# rxfirst.net
KiCad netlist of a schematic drawn in EAGLE
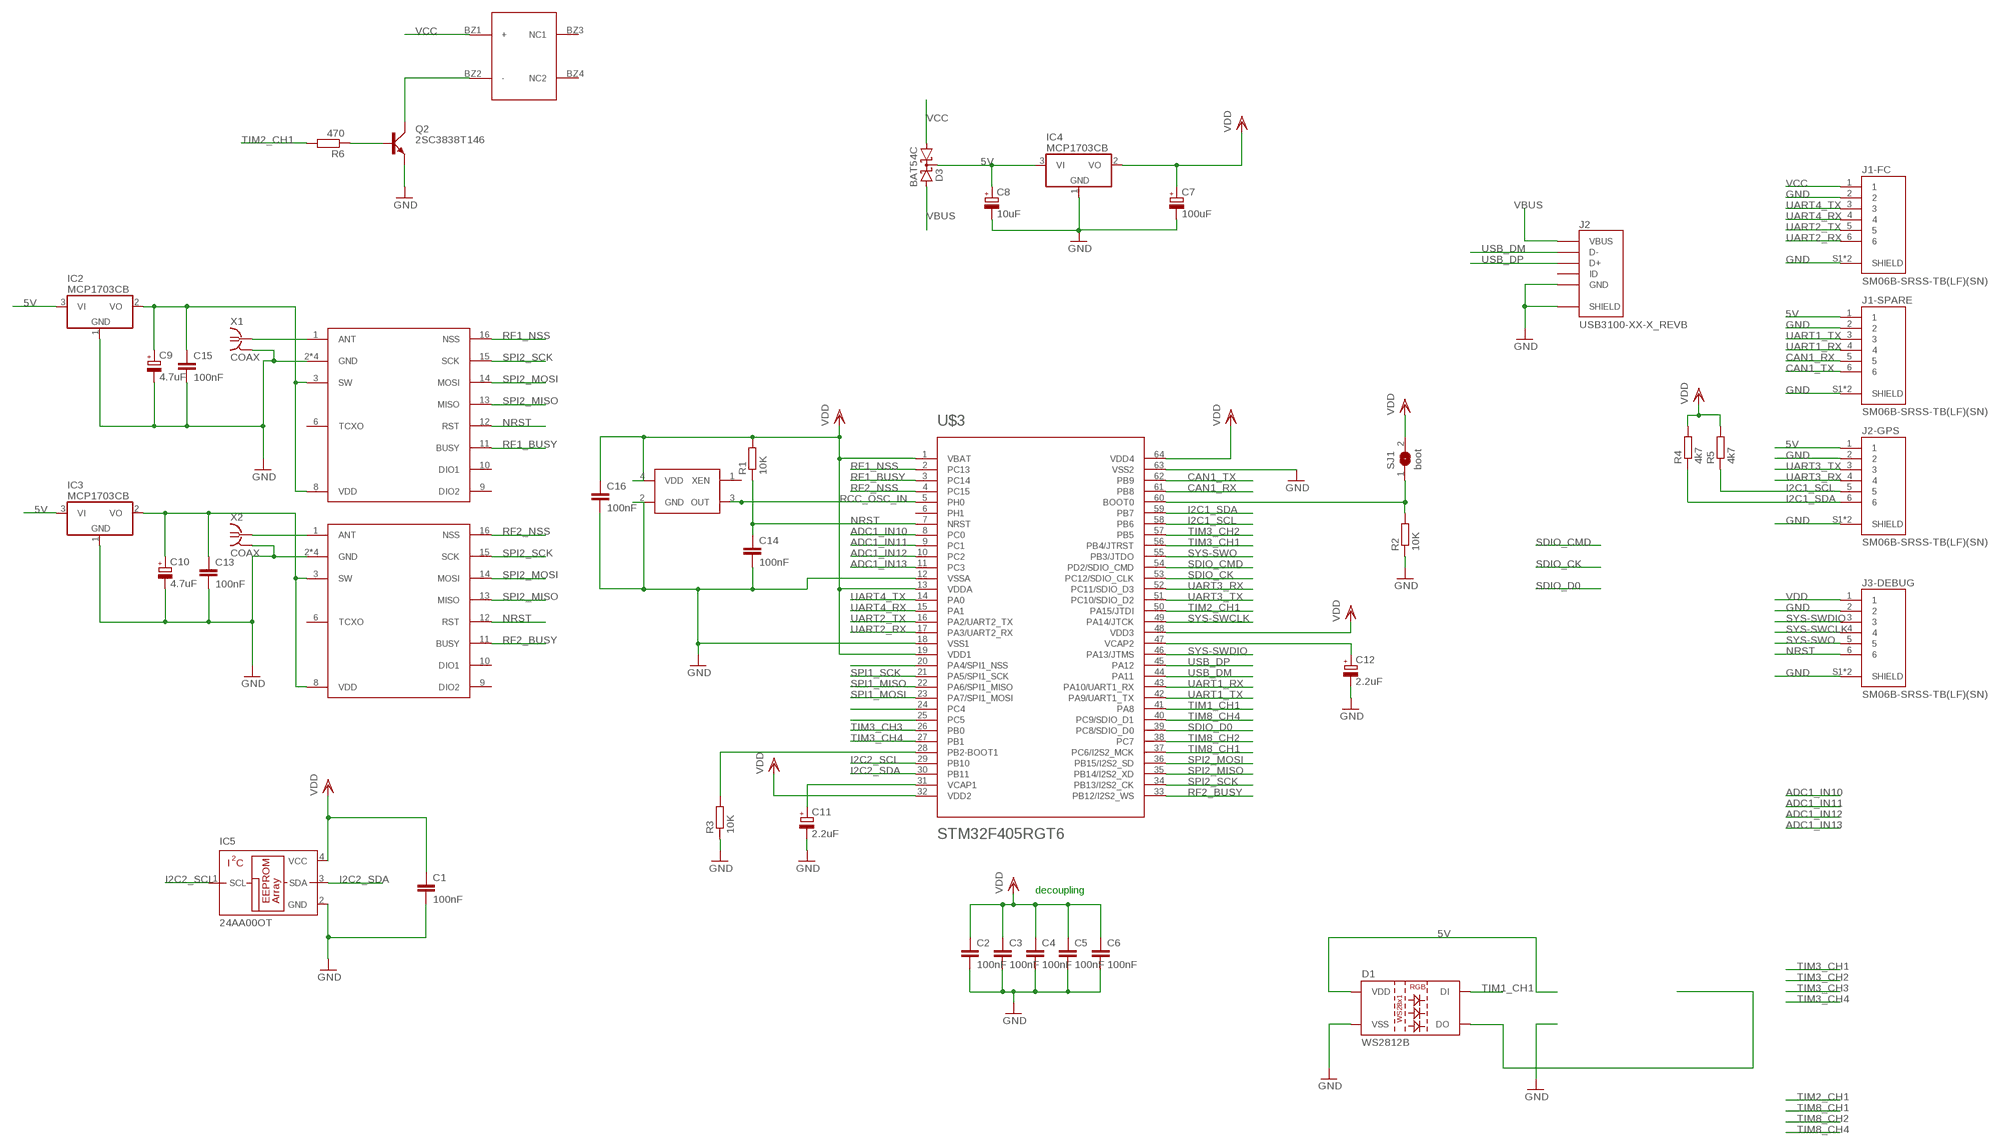
[diagram p0: schematic, sheet 1]

(export (version "E")
  (design (tool "Eeschema 10.0.6"))
  (components
    (comp (ref "C1")
      (value "100nF")
      (footprint "eagle-import:C0603")
      (libsource (lib "eagle-import") (part "C-EUC0603"))
    )
    (comp (ref "C2")
      (value "100nF")
      (footprint "eagle-import:C0603")
      (libsource (lib "eagle-import") (part "C-EUC0603"))
    )
    (comp (ref "C3")
      (value "100nF")
      (footprint "eagle-import:C0603")
      (libsource (lib "eagle-import") (part "C-EUC0603"))
    )
    (comp (ref "C4")
      (value "100nF")
      (footprint "eagle-import:C0603")
      (libsource (lib "eagle-import") (part "C-EUC0603"))
    )
    (comp (ref "C5")
      (value "100nF")
      (footprint "eagle-import:C0603")
      (libsource (lib "eagle-import") (part "C-EUC0603"))
    )
    (comp (ref "C6")
      (value "100nF")
      (footprint "eagle-import:C0603")
      (libsource (lib "eagle-import") (part "C-EUC0603"))
    )
    (comp (ref "C7")
      (value "100uF")
      (footprint "eagle-import:SMC_A")
      (libsource (lib "eagle-import") (part "CPOL-EUSMCA"))
    )
    (comp (ref "C8")
      (value "10uF")
      (footprint "eagle-import:SMC_A")
      (libsource (lib "eagle-import") (part "CPOL-EUSMCA"))
    )
    (comp (ref "C9")
      (value "4.7uF")
      (footprint "eagle-import:SMC_A")
      (libsource (lib "eagle-import") (part "CPOL-EUSMCA"))
    )
    (comp (ref "C10")
      (value "4.7uF")
      (footprint "eagle-import:SMC_A")
      (libsource (lib "eagle-import") (part "CPOL-EUSMCA"))
    )
    (comp (ref "C11")
      (value "2.2uF")
      (footprint "eagle-import:SMC_A")
      (libsource (lib "eagle-import") (part "CPOL-EUSMCA"))
    )
    (comp (ref "C12")
      (value "2.2uF")
      (footprint "eagle-import:SMC_A")
      (libsource (lib "eagle-import") (part "CPOL-EUSMCA"))
    )
    (comp (ref "C13")
      (value "100nF")
      (footprint "eagle-import:C0603")
      (libsource (lib "eagle-import") (part "C-EUC0603"))
    )
    (comp (ref "C14")
      (value "100nF")
      (footprint "eagle-import:C0603")
      (libsource (lib "eagle-import") (part "C-EUC0603"))
    )
    (comp (ref "C15")
      (value "100nF")
      (footprint "eagle-import:C0603")
      (libsource (lib "eagle-import") (part "C-EUC0603"))
    )
    (comp (ref "C16")
      (value "100nF")
      (footprint "eagle-import:C0603")
      (libsource (lib "eagle-import") (part "C-EUC0603"))
    )
    (comp (ref "D1")
      (value "WS2812B")
      (footprint "eagle-import:WS2812B")
      (libsource (lib "eagle-import") (part "WS2812B"))
    )
    (comp (ref "D3")
      (value "BAT54C")
      (footprint "eagle-import:SOT23")
      (libsource (lib "eagle-import") (part "BAT54C"))
    )
    (comp (ref "IC2")
      (value "MCP1703CB")
      (footprint "eagle-import:SOT23")
      (libsource (lib "eagle-import") (part "MCP1703CB"))
    )
    (comp (ref "IC3")
      (value "MCP1703CB")
      (footprint "eagle-import:SOT23")
      (libsource (lib "eagle-import") (part "MCP1703CB"))
    )
    (comp (ref "IC4")
      (value "MCP1703CB")
      (footprint "eagle-import:SOT23")
      (libsource (lib "eagle-import") (part "MCP1703CB"))
    )
    (comp (ref "IC5")
      (value "24AA00OT")
      (footprint "eagle-import:SOT23-5L")
      (fields (field (name "MF") "MICROCHIP") (field (name "MPN") "24AA00T-I/OTG"))
      (libsource (lib "eagle-import") (part "2400OTAA"))
    )
    (comp (ref "J1-FC")
      (value "SM06B-SRSS-TB(LF)(SN)")
      (footprint "eagle-import:JST_SM06B-SRSS-TB(LF)(SN)")
      (fields (field (name "MF") "JST Sales") (field (name "MP") "SM06B-SRSS-TB_LF__SN_"))
      (libsource (lib "eagle-import") (part "SM06B-SRSS-TB(LF)(SN)"))
    )
    (comp (ref "J1-SPARE")
      (value "SM06B-SRSS-TB(LF)(SN)")
      (footprint "eagle-import:JST_SM06B-SRSS-TB(LF)(SN)")
      (fields (field (name "MF") "JST Sales") (field (name "MP") "SM06B-SRSS-TB_LF__SN_"))
      (libsource (lib "eagle-import") (part "SM06B-SRSS-TB(LF)(SN)"))
    )
    (comp (ref "J2")
      (value "USB3100-XX-X_REVB")
      (footprint "eagle-import:GCT_USB3100-XX-X_REVB")
      (fields (field (name "MF") "Global Connector Technology") (field (name "MP") "USB3100-30-A"))
      (libsource (lib "eagle-import") (part "USB3100-XX-X_REVB"))
    )
    (comp (ref "J2-GPS")
      (value "SM06B-SRSS-TB(LF)(SN)")
      (footprint "eagle-import:JST_SM06B-SRSS-TB(LF)(SN)")
      (fields (field (name "MF") "JST Sales") (field (name "MP") "SM06B-SRSS-TB_LF__SN_"))
      (libsource (lib "eagle-import") (part "SM06B-SRSS-TB(LF)(SN)"))
    )
    (comp (ref "J3-DEBUG")
      (value "SM06B-SRSS-TB(LF)(SN)")
      (footprint "eagle-import:JST_SM06B-SRSS-TB(LF)(SN)")
      (fields (field (name "MF") "JST Sales") (field (name "MP") "SM06B-SRSS-TB_LF__SN_"))
      (libsource (lib "eagle-import") (part "SM06B-SRSS-TB(LF)(SN)"))
    )
    (comp (ref "Q2")
      (value "2SC3838T146")
      (footprint "eagle-import:SC59")
      (libsource (lib "eagle-import") (part "2SC3838T146"))
    )
    (comp (ref "R1")
      (value "10K")
      (footprint "eagle-import:R0603")
      (libsource (lib "eagle-import") (part "R-EU_R0603"))
    )
    (comp (ref "R2")
      (value "10K")
      (footprint "eagle-import:R0603")
      (libsource (lib "eagle-import") (part "R-EU_R0603"))
    )
    (comp (ref "R3")
      (value "10K")
      (footprint "eagle-import:R0603")
      (libsource (lib "eagle-import") (part "R-EU_R0603"))
    )
    (comp (ref "R4")
      (value "4k7")
      (footprint "eagle-import:R0603")
      (libsource (lib "eagle-import") (part "R-EU_R0603"))
    )
    (comp (ref "R5")
      (value "4k7")
      (footprint "eagle-import:R0603")
      (libsource (lib "eagle-import") (part "R-EU_R0603"))
    )
    (comp (ref "R6")
      (value "470")
      (footprint "eagle-import:R0603")
      (libsource (lib "eagle-import") (part "R-EU_R0603"))
    )
    (comp (ref "RF1")
      (value "DRF1262T")
      (footprint "eagle-import:SMD")
      (libsource (lib "eagle-import") (part "DRF1262T"))
    )
    (comp (ref "RF2")
      (value "DRF1262T")
      (footprint "eagle-import:SMD")
      (libsource (lib "eagle-import") (part "DRF1262T"))
    )
    (comp (ref "SJ1")
      (value "boot")
      (footprint "eagle-import:SJ")
      (libsource (lib "eagle-import") (part "SJ"))
    )
    (comp (ref "U$1")
      (value "BZ")
      (footprint "eagle-import:SND")
      (libsource (lib "eagle-import") (part "BZ"))
    )
    (comp (ref "U$3")
      (value "STM32F405RGT6")
      (footprint "eagle-import:TQFP64")
      (libsource (lib "eagle-import") (part "STM32F405RG"))
    )
    (comp (ref "U$4")
      (value "XO")
      (footprint "eagle-import:SMD")
      (libsource (lib "eagle-import") (part "XO"))
    )
    (comp (ref "X1")
      (value "COAX")
      (footprint "eagle-import:MMCX-J-P-X-ST-EM1-MKT")
      (fields (field (name "MF") "Samtec Inc.") (field (name "MPN") "MMCX-J-P-X-ST-EM1-MKT"))
      (libsource (lib "eagle-import") (part "COAX"))
    )
    (comp (ref "X2")
      (value "COAX")
      (footprint "eagle-import:MMCX-J-P-X-ST-EM1-MKT")
      (fields (field (name "MF") "Samtec Inc.") (field (name "MPN") "MMCX-J-P-X-ST-EM1-MKT"))
      (libsource (lib "eagle-import") (part "COAX"))
    )
  )
  (nets
    (net (code "1") (name "/5V") (class "Default")
      (node (ref "C8") (pin "+") (pinfunction "+_+") (pintype "passive"))
      (node (ref "D1") (pin "1") (pinfunction "VDD_1") (pintype "bidirectional"))
      (node (ref "D3") (pin "3") (pinfunction "CC_3") (pintype "passive"))
      (node (ref "IC2") (pin "3") (pinfunction "VI_3") (pintype "input"))
      (node (ref "IC3") (pin "3") (pinfunction "VI_3") (pintype "input"))
      (node (ref "IC4") (pin "3") (pinfunction "VI_3") (pintype "input"))
      (node (ref "J1-SPARE") (pin "1") (pinfunction "1_1") (pintype "passive"))
      (node (ref "J2-GPS") (pin "1") (pinfunction "1_1") (pintype "passive"))
    )
    (net (code "2") (name "/ADC1_IN10") (class "Default")
      (node (ref "U$3") (pin "8") (pinfunction "PC0_8") (pintype "bidirectional"))
    )
    (net (code "3") (name "/ADC1_IN11") (class "Default")
      (node (ref "U$3") (pin "9") (pinfunction "PC1_9") (pintype "bidirectional"))
    )
    (net (code "4") (name "/ADC1_IN12") (class "Default")
      (node (ref "U$3") (pin "10") (pinfunction "PC2_10") (pintype "bidirectional"))
    )
    (net (code "5") (name "/ADC1_IN13") (class "Default")
      (node (ref "U$3") (pin "11") (pinfunction "PC3_11") (pintype "bidirectional"))
    )
    (net (code "6") (name "/CAN1_RX") (class "Default")
      (node (ref "J1-SPARE") (pin "5") (pinfunction "5_5") (pintype "passive"))
      (node (ref "U$3") (pin "61") (pinfunction "PB8_61") (pintype "bidirectional"))
    )
    (net (code "7") (name "/CAN1_TX") (class "Default")
      (node (ref "J1-SPARE") (pin "6") (pinfunction "6_6") (pintype "passive"))
      (node (ref "U$3") (pin "62") (pinfunction "PB9_62") (pintype "bidirectional"))
    )
    (net (code "8") (name "/I2C1_SCL") (class "Default")
      (node (ref "J2-GPS") (pin "5") (pinfunction "5_5") (pintype "passive"))
      (node (ref "R5") (pin "1") (pinfunction "1_1") (pintype "passive"))
      (node (ref "U$3") (pin "58") (pinfunction "PB6_58") (pintype "bidirectional"))
    )
    (net (code "9") (name "/I2C1_SDA") (class "Default")
      (node (ref "J2-GPS") (pin "6") (pinfunction "6_6") (pintype "passive"))
      (node (ref "R4") (pin "1") (pinfunction "1_1") (pintype "passive"))
      (node (ref "U$3") (pin "59") (pinfunction "PB7_59") (pintype "bidirectional"))
    )
    (net (code "10") (name "/I2C2_SCL") (class "Default")
      (node (ref "IC5") (pin "1") (pinfunction "SCL_1") (pintype "input"))
      (node (ref "U$3") (pin "29") (pinfunction "PB10_29") (pintype "bidirectional"))
    )
    (net (code "11") (name "/I2C2_SDA") (class "Default")
      (node (ref "IC5") (pin "3") (pinfunction "SDA_3") (pintype "bidirectional"))
      (node (ref "U$3") (pin "30") (pinfunction "PB11_30") (pintype "bidirectional"))
    )
    (net (code "12") (name "/NRST") (class "Default")
      (node (ref "C14") (pin "1") (pinfunction "1_1") (pintype "passive"))
      (node (ref "J3-DEBUG") (pin "6") (pinfunction "6_6") (pintype "passive"))
      (node (ref "R1") (pin "1") (pinfunction "1_1") (pintype "passive"))
      (node (ref "RF1") (pin "12") (pinfunction "RST_12") (pintype "bidirectional"))
      (node (ref "RF2") (pin "12") (pinfunction "RST_12") (pintype "bidirectional"))
      (node (ref "U$3") (pin "7") (pinfunction "NRST_7") (pintype "bidirectional"))
    )
    (net (code "13") (name "/RCC_OSC_IN") (class "Default")
      (node (ref "U$3") (pin "5") (pinfunction "PH0_5") (pintype "bidirectional"))
      (node (ref "U$4") (pin "3") (pinfunction "OUT_3") (pintype "bidirectional"))
    )
    (net (code "14") (name "/RF1_BUSY") (class "Default")
      (node (ref "RF1") (pin "11") (pinfunction "BUSY_11") (pintype "output"))
      (node (ref "U$3") (pin "3") (pinfunction "PC14_3") (pintype "bidirectional"))
    )
    (net (code "15") (name "/RF1_NSS") (class "Default")
      (node (ref "RF1") (pin "16") (pinfunction "NSS_16") (pintype "bidirectional"))
      (node (ref "U$3") (pin "2") (pinfunction "PC13_2") (pintype "bidirectional"))
    )
    (net (code "16") (name "/RF2_BUSY") (class "Default")
      (node (ref "RF2") (pin "11") (pinfunction "BUSY_11") (pintype "output"))
      (node (ref "U$3") (pin "33") (pinfunction "PB12/I2S2_WS_33") (pintype "bidirectional"))
    )
    (net (code "17") (name "/RF2_NSS") (class "Default")
      (node (ref "RF2") (pin "16") (pinfunction "NSS_16") (pintype "bidirectional"))
      (node (ref "U$3") (pin "4") (pinfunction "PC15_4") (pintype "bidirectional"))
    )
    (net (code "18") (name "/SDIO_CK") (class "Default")
      (node (ref "U$3") (pin "53") (pinfunction "PC12/SDIO_CLK_53") (pintype "bidirectional"))
    )
    (net (code "19") (name "/SDIO_CMD") (class "Default")
      (node (ref "U$3") (pin "54") (pinfunction "PD2/SDIO_CMD_54") (pintype "bidirectional"))
    )
    (net (code "20") (name "/SDIO_D0") (class "Default")
      (node (ref "U$3") (pin "39") (pinfunction "PC8/SDIO_D0_39") (pintype "bidirectional"))
    )
    (net (code "21") (name "/SPI1_MISO") (class "Default")
      (node (ref "U$3") (pin "22") (pinfunction "PA6/SPI1_MISO_22") (pintype "bidirectional"))
    )
    (net (code "22") (name "/SPI1_MOSI") (class "Default")
      (node (ref "U$3") (pin "23") (pinfunction "PA7/SPI1_MOSI_23") (pintype "bidirectional"))
    )
    (net (code "23") (name "/SPI1_SCK") (class "Default")
      (node (ref "U$3") (pin "21") (pinfunction "PA5/SPI1_SCK_21") (pintype "bidirectional"))
    )
    (net (code "24") (name "/SPI2_MISO") (class "Default")
      (node (ref "RF1") (pin "13") (pinfunction "MISO_13") (pintype "output"))
      (node (ref "RF2") (pin "13") (pinfunction "MISO_13") (pintype "output"))
      (node (ref "U$3") (pin "35") (pinfunction "PB14/I2S2_XD_35") (pintype "bidirectional"))
    )
    (net (code "25") (name "/SPI2_MOSI") (class "Default")
      (node (ref "RF1") (pin "14") (pinfunction "MOSI_14") (pintype "bidirectional"))
      (node (ref "RF2") (pin "14") (pinfunction "MOSI_14") (pintype "bidirectional"))
      (node (ref "U$3") (pin "36") (pinfunction "PB15/I2S2_SD_36") (pintype "bidirectional"))
    )
    (net (code "26") (name "/SPI2_SCK") (class "Default")
      (node (ref "RF1") (pin "15") (pinfunction "SCK_15") (pintype "bidirectional"))
      (node (ref "RF2") (pin "15") (pinfunction "SCK_15") (pintype "bidirectional"))
      (node (ref "U$3") (pin "34") (pinfunction "PB13/I2S2_CK_34") (pintype "bidirectional"))
    )
    (net (code "27") (name "/SYS-SWCLK") (class "Default")
      (node (ref "J3-DEBUG") (pin "4") (pinfunction "4_4") (pintype "passive"))
      (node (ref "U$3") (pin "49") (pinfunction "PA14/JTCK_49") (pintype "bidirectional"))
    )
    (net (code "28") (name "/SYS-SWDIO") (class "Default")
      (node (ref "J3-DEBUG") (pin "3") (pinfunction "3_3") (pintype "passive"))
      (node (ref "U$3") (pin "46") (pinfunction "PA13/JTMS_46") (pintype "bidirectional"))
    )
    (net (code "29") (name "/SYS-SWO") (class "Default")
      (node (ref "J3-DEBUG") (pin "5") (pinfunction "5_5") (pintype "passive"))
      (node (ref "U$3") (pin "55") (pinfunction "PB3/JTDO_55") (pintype "bidirectional"))
    )
    (net (code "30") (name "/TIM1_CH1") (class "Default")
      (node (ref "D1") (pin "4") (pinfunction "DI_4") (pintype "bidirectional"))
      (node (ref "U$3") (pin "41") (pinfunction "PA8_41") (pintype "bidirectional"))
    )
    (net (code "31") (name "/TIM2_CH1") (class "Default")
      (node (ref "R6") (pin "2") (pinfunction "2_2") (pintype "passive"))
      (node (ref "U$3") (pin "50") (pinfunction "PA15/JTDI_50") (pintype "bidirectional"))
    )
    (net (code "32") (name "/TIM3_CH1") (class "Default")
      (node (ref "U$3") (pin "56") (pinfunction "PB4/JTRST_56") (pintype "bidirectional"))
    )
    (net (code "33") (name "/TIM3_CH2") (class "Default")
      (node (ref "U$3") (pin "57") (pinfunction "PB5_57") (pintype "bidirectional"))
    )
    (net (code "34") (name "/TIM3_CH3") (class "Default")
      (node (ref "U$3") (pin "26") (pinfunction "PB0_26") (pintype "bidirectional"))
    )
    (net (code "35") (name "/TIM3_CH4") (class "Default")
      (node (ref "U$3") (pin "27") (pinfunction "PB1_27") (pintype "bidirectional"))
    )
    (net (code "36") (name "/TIM8_CH1") (class "Default")
      (node (ref "U$3") (pin "37") (pinfunction "PC6/I2S2_MCK_37") (pintype "bidirectional"))
    )
    (net (code "37") (name "/TIM8_CH2") (class "Default")
      (node (ref "U$3") (pin "38") (pinfunction "PC7_38") (pintype "bidirectional"))
    )
    (net (code "38") (name "/TIM8_CH4") (class "Default")
      (node (ref "U$3") (pin "40") (pinfunction "PC9/SDIO_D1_40") (pintype "bidirectional"))
    )
    (net (code "39") (name "/UART1_RX") (class "Default")
      (node (ref "J1-SPARE") (pin "4") (pinfunction "4_4") (pintype "passive"))
      (node (ref "U$3") (pin "43") (pinfunction "PA10/UART1_RX_43") (pintype "bidirectional"))
    )
    (net (code "40") (name "/UART1_TX") (class "Default")
      (node (ref "J1-SPARE") (pin "3") (pinfunction "3_3") (pintype "passive"))
      (node (ref "U$3") (pin "42") (pinfunction "PA9/UART1_TX_42") (pintype "bidirectional"))
    )
    (net (code "41") (name "/UART2_RX") (class "Default")
      (node (ref "J1-FC") (pin "6") (pinfunction "6_6") (pintype "passive"))
      (node (ref "U$3") (pin "17") (pinfunction "PA3/UART2_RX_17") (pintype "bidirectional"))
    )
    (net (code "42") (name "/UART2_TX") (class "Default")
      (node (ref "J1-FC") (pin "5") (pinfunction "5_5") (pintype "passive"))
      (node (ref "U$3") (pin "16") (pinfunction "PA2/UART2_TX_16") (pintype "bidirectional"))
    )
    (net (code "43") (name "/UART3_RX") (class "Default")
      (node (ref "J2-GPS") (pin "4") (pinfunction "4_4") (pintype "passive"))
      (node (ref "U$3") (pin "52") (pinfunction "PC11/SDIO_D3_52") (pintype "bidirectional"))
    )
    (net (code "44") (name "/UART3_TX") (class "Default")
      (node (ref "J2-GPS") (pin "3") (pinfunction "3_3") (pintype "passive"))
      (node (ref "U$3") (pin "51") (pinfunction "PC10/SDIO_D2_51") (pintype "bidirectional"))
    )
    (net (code "45") (name "/UART4_RX") (class "Default")
      (node (ref "J1-FC") (pin "4") (pinfunction "4_4") (pintype "passive"))
      (node (ref "U$3") (pin "15") (pinfunction "PA1_15") (pintype "bidirectional"))
    )
    (net (code "46") (name "/UART4_TX") (class "Default")
      (node (ref "J1-FC") (pin "3") (pinfunction "3_3") (pintype "passive"))
      (node (ref "U$3") (pin "14") (pinfunction "PA0_14") (pintype "bidirectional"))
    )
    (net (code "47") (name "/USB_DM") (class "Default")
      (node (ref "J2") (pin "2") (pinfunction "D-_2") (pintype "bidirectional"))
      (node (ref "U$3") (pin "44") (pinfunction "PA11_44") (pintype "bidirectional"))
    )
    (net (code "48") (name "/USB_DP") (class "Default")
      (node (ref "J2") (pin "3") (pinfunction "D+_3") (pintype "bidirectional"))
      (node (ref "U$3") (pin "45") (pinfunction "PA12_45") (pintype "bidirectional"))
    )
    (net (code "49") (name "/VBUS") (class "Default")
      (node (ref "D3") (pin "2") (pinfunction "A2_2") (pintype "passive"))
      (node (ref "J2") (pin "1") (pinfunction "VBUS_1") (pintype "power_in"))
    )
    (net (code "50") (name "/VCC") (class "Default")
      (node (ref "D3") (pin "1") (pinfunction "A1_1") (pintype "passive"))
      (node (ref "J1-FC") (pin "1") (pinfunction "1_1") (pintype "passive"))
      (node (ref "U$1") (pin "BZ1") (pinfunction "+_BZ1") (pintype "bidirectional"))
    )
    (net (code "51") (name "GND") (class "Default")
      (node (ref "C1") (pin "2") (pinfunction "2_2") (pintype "passive"))
      (node (ref "C10") (pin "-") (pinfunction "-_-") (pintype "passive"))
      (node (ref "C11") (pin "-") (pinfunction "-_-") (pintype "passive"))
      (node (ref "C12") (pin "-") (pinfunction "-_-") (pintype "passive"))
      (node (ref "C13") (pin "2") (pinfunction "2_2") (pintype "passive"))
      (node (ref "C14") (pin "2") (pinfunction "2_2") (pintype "passive"))
      (node (ref "C15") (pin "2") (pinfunction "2_2") (pintype "passive"))
      (node (ref "C16") (pin "2") (pinfunction "2_2") (pintype "passive"))
      (node (ref "C2") (pin "2") (pinfunction "2_2") (pintype "passive"))
      (node (ref "C3") (pin "2") (pinfunction "2_2") (pintype "passive"))
      (node (ref "C4") (pin "2") (pinfunction "2_2") (pintype "passive"))
      (node (ref "C5") (pin "2") (pinfunction "2_2") (pintype "passive"))
      (node (ref "C6") (pin "2") (pinfunction "2_2") (pintype "passive"))
      (node (ref "C7") (pin "-") (pinfunction "-_-") (pintype "passive"))
      (node (ref "C8") (pin "-") (pinfunction "-_-") (pintype "passive"))
      (node (ref "C9") (pin "-") (pinfunction "-_-") (pintype "passive"))
      (node (ref "D1") (pin "3") (pinfunction "VSS_3") (pintype "bidirectional"))
      (node (ref "IC2") (pin "1") (pinfunction "GND_1") (pintype "passive"))
      (node (ref "IC3") (pin "1") (pinfunction "GND_1") (pintype "passive"))
      (node (ref "IC4") (pin "1") (pinfunction "GND_1") (pintype "passive"))
      (node (ref "IC5") (pin "2") (pinfunction "GND_2") (pintype "power_in"))
      (node (ref "J1-FC") (pin "2") (pinfunction "2_2") (pintype "passive"))
      (node (ref "J1-FC") (pin "S1") (pinfunction "SHIELD_S1") (pintype "passive"))
      (node (ref "J1-FC") (pin "S2") (pinfunction "SHIELD_S2") (pintype "passive"))
      (node (ref "J1-SPARE") (pin "2") (pinfunction "2_2") (pintype "passive"))
      (node (ref "J1-SPARE") (pin "S1") (pinfunction "SHIELD_S1") (pintype "passive"))
      (node (ref "J1-SPARE") (pin "S2") (pinfunction "SHIELD_S2") (pintype "passive"))
      (node (ref "J2") (pin "5") (pinfunction "GND_5") (pintype "power_in"))
      (node (ref "J2") (pin "6") (pinfunction "SHIELD_6") (pintype "power_in"))
      (node (ref "J2") (pin "7") (pinfunction "SHIELD_7") (pintype "power_in"))
      (node (ref "J2") (pin "8") (pinfunction "SHIELD_8") (pintype "power_in"))
      (node (ref "J2") (pin "9") (pinfunction "SHIELD_9") (pintype "power_in"))
      (node (ref "J2-GPS") (pin "2") (pinfunction "2_2") (pintype "passive"))
      (node (ref "J2-GPS") (pin "S1") (pinfunction "SHIELD_S1") (pintype "passive"))
      (node (ref "J2-GPS") (pin "S2") (pinfunction "SHIELD_S2") (pintype "passive"))
      (node (ref "J3-DEBUG") (pin "2") (pinfunction "2_2") (pintype "passive"))
      (node (ref "J3-DEBUG") (pin "S1") (pinfunction "SHIELD_S1") (pintype "passive"))
      (node (ref "J3-DEBUG") (pin "S2") (pinfunction "SHIELD_S2") (pintype "passive"))
      (node (ref "Q2") (pin "E") (pinfunction "E_E") (pintype "passive"))
      (node (ref "R2") (pin "1") (pinfunction "1_1") (pintype "passive"))
      (node (ref "R3") (pin "1") (pinfunction "1_1") (pintype "passive"))
      (node (ref "RF1") (pin "2") (pinfunction "GND_2") (pintype "power_in"))
      (node (ref "RF1") (pin "4") (pinfunction "GND_4") (pintype "power_in"))
      (node (ref "RF1") (pin "5") (pinfunction "GND_5") (pintype "power_in"))
      (node (ref "RF1") (pin "7") (pinfunction "GND_7") (pintype "power_in"))
      (node (ref "RF2") (pin "2") (pinfunction "GND_2") (pintype "power_in"))
      (node (ref "RF2") (pin "4") (pinfunction "GND_4") (pintype "power_in"))
      (node (ref "RF2") (pin "5") (pinfunction "GND_5") (pintype "power_in"))
      (node (ref "RF2") (pin "7") (pinfunction "GND_7") (pintype "power_in"))
      (node (ref "U$3") (pin "12") (pinfunction "VSSA_12") (pintype "bidirectional"))
      (node (ref "U$3") (pin "18") (pinfunction "VSS1_18") (pintype "bidirectional"))
      (node (ref "U$3") (pin "63") (pinfunction "VSS2_63") (pintype "bidirectional"))
      (node (ref "U$4") (pin "2") (pinfunction "GND_2") (pintype "bidirectional"))
      (node (ref "X1") (pin "2@1") (pinfunction "GND_2@1") (pintype "power_in"))
      (node (ref "X2") (pin "2@1") (pinfunction "GND_2@1") (pintype "power_in"))
    )
    (net (code "52") (name "Net-(IC2-VO)") (class "Default")
      (node (ref "C15") (pin "1") (pinfunction "1_1") (pintype "passive"))
      (node (ref "C9") (pin "+") (pinfunction "+_+") (pintype "passive"))
      (node (ref "IC2") (pin "2") (pinfunction "VO_2") (pintype "passive"))
      (node (ref "RF1") (pin "3") (pinfunction "SW_3") (pintype "bidirectional"))
      (node (ref "RF1") (pin "8") (pinfunction "VDD_8") (pintype "power_in"))
    )
    (net (code "53") (name "Net-(IC3-VO)") (class "Default")
      (node (ref "C10") (pin "+") (pinfunction "+_+") (pintype "passive"))
      (node (ref "C13") (pin "1") (pinfunction "1_1") (pintype "passive"))
      (node (ref "IC3") (pin "2") (pinfunction "VO_2") (pintype "passive"))
      (node (ref "RF2") (pin "3") (pinfunction "SW_3") (pintype "bidirectional"))
      (node (ref "RF2") (pin "8") (pinfunction "VDD_8") (pintype "power_in"))
    )
    (net (code "54") (name "Net-(Q2-PadB)") (class "Default")
      (node (ref "Q2") (pin "B") (pinfunction "B_B") (pintype "passive"))
      (node (ref "R6") (pin "1") (pinfunction "1_1") (pintype "passive"))
    )
    (net (code "55") (name "Net-(RF1-ANT)") (class "Default")
      (node (ref "RF1") (pin "1") (pinfunction "ANT_1") (pintype "output"))
      (node (ref "X1") (pin "1") (pinfunction "1_1") (pintype "passive"))
    )
    (net (code "56") (name "Net-(RF2-ANT)") (class "Default")
      (node (ref "RF2") (pin "1") (pinfunction "ANT_1") (pintype "output"))
      (node (ref "X2") (pin "1") (pinfunction "1_1") (pintype "passive"))
    )
    (net (code "57") (name "Net-(U$1--)") (class "Default")
      (node (ref "Q2") (pin "C") (pinfunction "C_C") (pintype "passive"))
      (node (ref "U$1") (pin "BZ2") (pinfunction "-_BZ2") (pintype "bidirectional"))
    )
    (net (code "58") (name "Net-(U$3-BOOT0)") (class "Default")
      (node (ref "R2") (pin "2") (pinfunction "2_2") (pintype "passive"))
      (node (ref "SJ1") (pin "1") (pinfunction "1_1") (pintype "passive"))
      (node (ref "U$3") (pin "60") (pinfunction "BOOT0_60") (pintype "bidirectional"))
    )
    (net (code "59") (name "Net-(U$3-PB2-BOOT1)") (class "Default")
      (node (ref "R3") (pin "2") (pinfunction "2_2") (pintype "passive"))
      (node (ref "U$3") (pin "28") (pinfunction "PB2-BOOT1_28") (pintype "bidirectional"))
    )
    (net (code "60") (name "Net-(U$3-VCAP1)") (class "Default")
      (node (ref "C11") (pin "+") (pinfunction "+_+") (pintype "passive"))
      (node (ref "U$3") (pin "31") (pinfunction "VCAP1_31") (pintype "bidirectional"))
    )
    (net (code "61") (name "Net-(U$3-VCAP2)") (class "Default")
      (node (ref "C12") (pin "+") (pinfunction "+_+") (pintype "passive"))
      (node (ref "U$3") (pin "47") (pinfunction "VCAP2_47") (pintype "bidirectional"))
    )
    (net (code "62") (name "VDD") (class "Default")
      (node (ref "C1") (pin "1") (pinfunction "1_1") (pintype "passive"))
      (node (ref "C16") (pin "1") (pinfunction "1_1") (pintype "passive"))
      (node (ref "C2") (pin "1") (pinfunction "1_1") (pintype "passive"))
      (node (ref "C3") (pin "1") (pinfunction "1_1") (pintype "passive"))
      (node (ref "C4") (pin "1") (pinfunction "1_1") (pintype "passive"))
      (node (ref "C5") (pin "1") (pinfunction "1_1") (pintype "passive"))
      (node (ref "C6") (pin "1") (pinfunction "1_1") (pintype "passive"))
      (node (ref "C7") (pin "+") (pinfunction "+_+") (pintype "passive"))
      (node (ref "IC4") (pin "2") (pinfunction "VO_2") (pintype "passive"))
      (node (ref "IC5") (pin "4") (pinfunction "VCC_4") (pintype "power_in"))
      (node (ref "J3-DEBUG") (pin "1") (pinfunction "1_1") (pintype "passive"))
      (node (ref "R1") (pin "2") (pinfunction "2_2") (pintype "passive"))
      (node (ref "R4") (pin "2") (pinfunction "2_2") (pintype "passive"))
      (node (ref "R5") (pin "2") (pinfunction "2_2") (pintype "passive"))
      (node (ref "SJ1") (pin "2") (pinfunction "2_2") (pintype "passive"))
      (node (ref "U$3") (pin "1") (pinfunction "VBAT_1") (pintype "bidirectional"))
      (node (ref "U$3") (pin "13") (pinfunction "VDDA_13") (pintype "bidirectional"))
      (node (ref "U$3") (pin "19") (pinfunction "VDD1_19") (pintype "bidirectional"))
      (node (ref "U$3") (pin "32") (pinfunction "VDD2_32") (pintype "bidirectional"))
      (node (ref "U$3") (pin "48") (pinfunction "VDD3_48") (pintype "bidirectional"))
      (node (ref "U$3") (pin "64") (pinfunction "VDD4_64") (pintype "bidirectional"))
      (node (ref "U$4") (pin "4") (pinfunction "VDD_4") (pintype "bidirectional"))
    )
    (net (code "63") (name "unconnected-(D1-DO-Pad2)") (class "Default")
      (node (ref "D1") (pin "2") (pinfunction "DO_2") (pintype "bidirectional"))
    )
    (net (code "64") (name "unconnected-(J2-ID-Pad4)") (class "Default")
      (node (ref "J2") (pin "4") (pinfunction "ID_4") (pintype "bidirectional"))
    )
    (net (code "65") (name "unconnected-(RF1-DIO1-Pad10)") (class "Default")
      (node (ref "RF1") (pin "10") (pinfunction "DIO1_10") (pintype "bidirectional"))
    )
    (net (code "66") (name "unconnected-(RF1-DIO2-Pad9)") (class "Default")
      (node (ref "RF1") (pin "9") (pinfunction "DIO2_9") (pintype "bidirectional"))
    )
    (net (code "67") (name "unconnected-(RF1-TCXO-Pad6)") (class "Default")
      (node (ref "RF1") (pin "6") (pinfunction "TCXO_6") (pintype "bidirectional"))
    )
    (net (code "68") (name "unconnected-(RF2-DIO1-Pad10)") (class "Default")
      (node (ref "RF2") (pin "10") (pinfunction "DIO1_10") (pintype "bidirectional"))
    )
    (net (code "69") (name "unconnected-(RF2-DIO2-Pad9)") (class "Default")
      (node (ref "RF2") (pin "9") (pinfunction "DIO2_9") (pintype "bidirectional"))
    )
    (net (code "70") (name "unconnected-(RF2-TCXO-Pad6)") (class "Default")
      (node (ref "RF2") (pin "6") (pinfunction "TCXO_6") (pintype "bidirectional"))
    )
    (net (code "71") (name "unconnected-(U$1-NC1-PadBZ3)") (class "Default")
      (node (ref "U$1") (pin "BZ3") (pinfunction "NC1_BZ3") (pintype "bidirectional"))
    )
    (net (code "72") (name "unconnected-(U$1-NC2-PadBZ4)") (class "Default")
      (node (ref "U$1") (pin "BZ4") (pinfunction "NC2_BZ4") (pintype "bidirectional"))
    )
    (net (code "73") (name "unconnected-(U$3-PA4{slash}SPI1_NSS-Pad20)") (class "Default")
      (node (ref "U$3") (pin "20") (pinfunction "PA4/SPI1_NSS_20") (pintype "bidirectional"))
    )
    (net (code "74") (name "unconnected-(U$3-PC4-Pad24)") (class "Default")
      (node (ref "U$3") (pin "24") (pinfunction "PC4_24") (pintype "bidirectional"))
    )
    (net (code "75") (name "unconnected-(U$3-PC5-Pad25)") (class "Default")
      (node (ref "U$3") (pin "25") (pinfunction "PC5_25") (pintype "bidirectional"))
    )
    (net (code "76") (name "unconnected-(U$3-PH1-Pad6)") (class "Default")
      (node (ref "U$3") (pin "6") (pinfunction "PH1_6") (pintype "bidirectional"))
    )
    (net (code "77") (name "unconnected-(U$4-XEN-Pad1)") (class "Default")
      (node (ref "U$4") (pin "1") (pinfunction "XEN_1") (pintype "bidirectional"))
    )
  )
)
